# project-light.net
KiCad netlist of a schematic drawn in Altium Designer
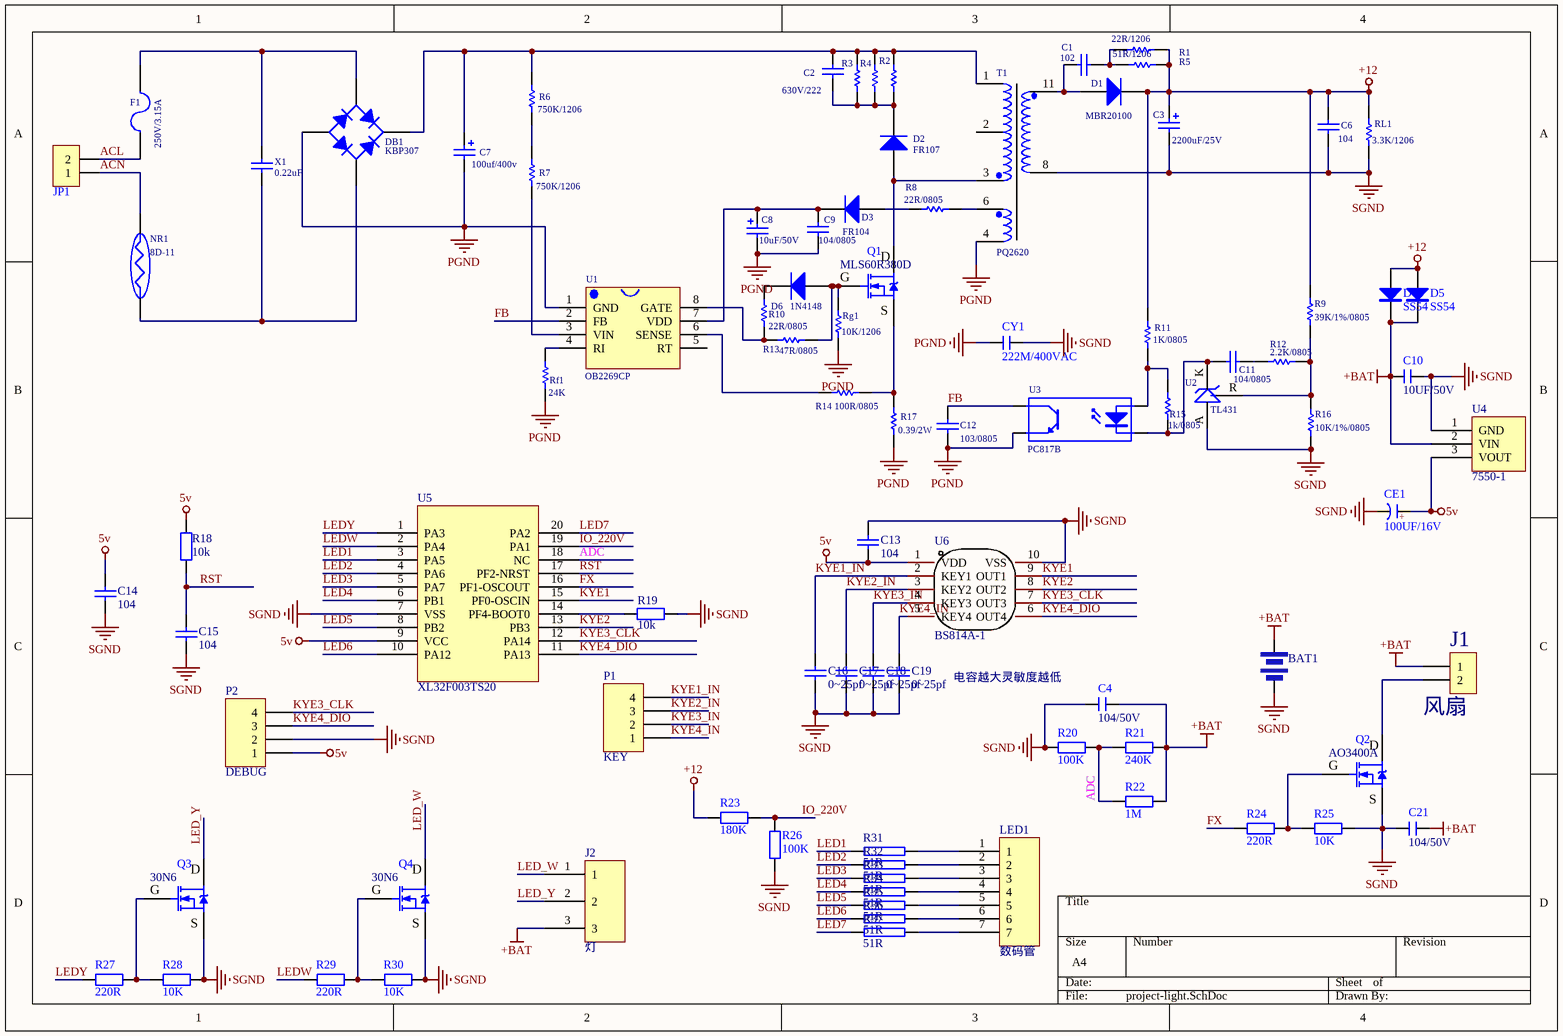
[diagram p0: project-light.SchDoc]

(export (version "E")
  (design (tool "Eeschema 10.0.6"))
  (components
    (comp (ref "BAT1") (value "~") (footprint "2pin") (libsource (lib "HOLIN") (part "BATTERY")))
    (comp (ref "C1")
      (value "102")
      (footprint "C 1206_l")
      (description "Capacitor")
      (fields (field (name "Comment") "472") (field (name "PUBLISHER") "Altium Limited"))
      (libsource (lib "Miscellaneous Devices") (part "Cap"))
    )
    (comp (ref "C2")
      (value "630V/222")
      (footprint "CBB=7.5MM")
      (description "Capacitor")
      (fields (field (name "PUBLISHER") "Altium Limited"))
      (libsource (lib "Miscellaneous Devices") (part "Cap"))
    )
    (comp (ref "C3")
      (value "2200uF/25V")
      (footprint "CAP 5.0*10*20-H - GD")
      (description "Polarized Capacitor (Axial)")
      (fields (field (name "PUBLISHER") "Altium Limited"))
      (libsource (lib "") (part "Cap Pol2_1"))
    )
    (comp (ref "C4")
      (value "104/50V")
      (footprint "C 0805_L")
      (description "瓷片电容")
      (libsource (lib "0.1 - 电阻-电容-电感") (part "CC"))
    )
    (comp (ref "C6")
      (value "104")
      (footprint "C 1206_l")
      (description "Capacitor")
      (fields (field (name "PUBLISHER") "Altium Limited"))
      (libsource (lib "Miscellaneous Devices") (part "Cap"))
    )
    (comp (ref "C7")
      (value "100uf/400v")
      (footprint "Cin /400V/56uF Wo")
      (description "Polarized Capacitor (Axial)")
      (fields (field (name "PUBLISHER") "Altium Limited"))
      (libsource (lib "Miscellaneous Devices") (part "Cap Pol2"))
    )
    (comp (ref "C8")
      (value "10uF/50V")
      (footprint "C Φ5*11 L=2.5")
      (description "Polarized Capacitor (Axial)")
      (fields (field (name "Comment") "47uF/50V") (field (name "PUBLISHER") "Altium Limited"))
      (libsource (lib "Miscellaneous Devices") (part "Cap Pol2"))
    )
    (comp (ref "C9")
      (value "104/0805")
      (footprint "C 0805_L")
      (description "Capacitor")
      (fields (field (name "PUBLISHER") "Altium Limited"))
      (libsource (lib "Miscellaneous Devices") (part "Cap"))
    )
    (comp (ref "C10")
      (value "10UF/50V")
      (footprint "C 0805_L")
      (description "瓷片电容")
      (libsource (lib "0.1 - 电阻-电容-电感") (part "CC"))
    )
    (comp (ref "C11")
      (value "104/0805")
      (footprint "C 0805_L")
      (description "Capacitor")
      (fields (field (name "PUBLISHER") "Altium Limited"))
      (libsource (lib "Miscellaneous Devices") (part "Cap"))
    )
    (comp (ref "C12")
      (value "103/0805")
      (footprint "C 0805_L")
      (description "Capacitor")
      (fields (field (name "PUBLISHER") "Altium Limited"))
      (libsource (lib "Miscellaneous Devices") (part "Cap"))
    )
    (comp (ref "C13")
      (value "104")
      (footprint "c 0805_l")
      (description "Capacitor")
      (fields (field (name "PUBLISHER") "Altium Limited"))
      (libsource (lib "Miscellaneous Devices") (part "Cap"))
    )
    (comp (ref "C14")
      (value "104")
      (footprint "C 0805_L")
      (description "Capacitor")
      (fields (field (name "PUBLISHER") "Altium Limited"))
      (libsource (lib "Miscellaneous Devices") (part "Cap"))
    )
    (comp (ref "C15")
      (value "104")
      (footprint "C 0805_L")
      (description "Capacitor")
      (fields (field (name "PUBLISHER") "Altium Limited"))
      (libsource (lib "Miscellaneous Devices") (part "Cap"))
    )
    (comp (ref "C16")
      (value "0~25pf")
      (footprint "C 0805_L")
      (description "Capacitor")
      (fields (field (name "PUBLISHER") "Altium Limited"))
      (libsource (lib "Miscellaneous Devices") (part "Cap"))
    )
    (comp (ref "C17")
      (value "0~25pf")
      (footprint "C 0805_L")
      (description "Capacitor")
      (fields (field (name "PUBLISHER") "Altium Limited"))
      (libsource (lib "Miscellaneous Devices") (part "Cap"))
    )
    (comp (ref "C18")
      (value "0~25pf")
      (footprint "C 0805_L")
      (description "Capacitor")
      (fields (field (name "PUBLISHER") "Altium Limited"))
      (libsource (lib "Miscellaneous Devices") (part "Cap"))
    )
    (comp (ref "C19")
      (value "0~25pf")
      (footprint "C 0805_L")
      (description "Capacitor")
      (fields (field (name "PUBLISHER") "Altium Limited"))
      (libsource (lib "Miscellaneous Devices") (part "Cap"))
    )
    (comp (ref "C21")
      (value "104/50V")
      (footprint "C 0805_L")
      (description "瓷片电容")
      (libsource (lib "0.1 - 电阻-电容-电感") (part "CC"))
    )
    (comp (ref "CE1")
      (value "100UF/16V")
      (footprint "CAP 2.5*6.3*11.2")
      (description "直插电解电容")
      (libsource (lib "0.1 - 电阻-电容-电感") (part "CE"))
    )
    (comp (ref "CY1")
      (value "222M/400VAC")
      (footprint "CY 7.5*8*4")
      (description "安规Y电容")
      (fields (field (name "版权归属") "封装库来自淘宝 ID：黄晶宝石"))
      (libsource (lib "0.1 - 电阻-电容-电感") (part "CY"))
    )
    (comp (ref "D1")
      (value "MBR20100")
      (footprint "TO252")
      (description "Silicon Low Leakage Diode")
      (fields (field (name "PUBLISHER") "Altium Limited"))
      (libsource (lib "Miscellaneous Devices") (part "Diode BAS116"))
    )
    (comp (ref "D2")
      (value "FR107")
      (footprint "D/SOD123")
      (description "Silicon Low Leakage Diode")
      (fields (field (name "PUBLISHER") "Altium Limited"))
      (libsource (lib "Miscellaneous Devices") (part "Diode BAS116"))
    )
    (comp (ref "D3")
      (value "FR104")
      (footprint "D/SOD123")
      (description "Silicon Low Leakage Diode")
      (fields (field (name "PUBLISHER") "Altium Limited"))
      (libsource (lib "Miscellaneous Devices") (part "Diode BAS116"))
    )
    (comp (ref "D4")
      (value "SS54")
      (footprint "SMA")
      (description "整流二极管")
      (libsource (lib "0.2 - 二极管-整流桥") (part "1N4007"))
    )
    (comp (ref "D5")
      (value "SS54")
      (footprint "SMA")
      (description "整流二极管")
      (libsource (lib "0.2 - 二极管-整流桥") (part "1N4007"))
    )
    (comp (ref "D6")
      (value "1N4148")
      (footprint "D 1N4148")
      (description "Silicon Low Leakage Diode")
      (fields (field (name "PUBLISHER") "Altium Limited"))
      (libsource (lib "") (part "Diode BAS116_1"))
    )
    (comp (ref "DB1")
      (value "KBP307")
      (footprint "DB D=1.1MM")
      (description "Full Wave Diode Bridge")
      (fields (field (name "PUBLISHER") "Altium Limited"))
      (libsource (lib "Miscellaneous Devices") (part "Bridge1"))
    )
    (comp (ref "F1")
      (value "250V/3.15A")
      (footprint "F 3.15A L=5MM")
      (description "Fuse")
      (fields (field (name "PUBLISHER") "Altium Limited"))
      (libsource (lib "Miscellaneous Devices") (part "Fuse 2"))
    )
    (comp (ref "J1")
      (value "风扇")
      (footprint "XH2.54-LI-2P")
      (description "Connector")
      (libsource (lib "*") (part "CON2"))
    )
    (comp (ref "J2") (value "灯") (footprint "HDR2.54-LI-3P") (libsource (lib "Schlib1") (part "Component_1")))
    (comp (ref "JP1")
      (value "HDR-1X2")
      (footprint "AC-027母座")
      (description "2P接插件")
      (fields (field (name "版权归属") "封装库来自淘宝 ID：黄晶宝石"))
      (libsource (lib "CFY01205") (part "Header 2"))
    )
    (comp (ref "LED1") (value "数码管") (footprint "1516数码管") (libsource (lib "CFY01205") (part "数码管")))
    (comp (ref "NR1") (value "8D-11") (footprint "NTC=7.5mm") (libsource (lib "12V5A") (part "NTC")))
    (comp (ref "P1")
      (value "KEY")
      (footprint "HDR1X4")
      (description "Header, 4-Pin")
      (fields (field (name "PUBLISHER") "Altium Limited"))
      (libsource (lib "Miscellaneous Connectors") (part "Header 4"))
    )
    (comp (ref "P2")
      (value "DEBUG")
      (footprint "HDR1X4")
      (description "Header, 4-Pin")
      (fields (field (name "PUBLISHER") "Altium Limited"))
      (libsource (lib "Miscellaneous Connectors") (part "Header 4"))
    )
    (comp (ref "Q1")
      (value "MLS60R380D")
      (footprint "TO252")
      (description "N沟场效应管")
      (libsource (lib "") (part "IRF840_1"))
    )
    (comp (ref "Q2")
      (value "AO3400A")
      (footprint "SOT-23")
      (description "N沟场效应管")
      (libsource (lib "0.5 - 场效应管-可控硅") (part "IRF840"))
    )
    (comp (ref "Q3")
      (value "30N6")
      (footprint "TO252")
      (description "N沟场效应管")
      (libsource (lib "") (part "IRF840_1"))
    )
    (comp (ref "Q4")
      (value "30N6")
      (footprint "TO252")
      (description "N沟场效应管")
      (libsource (lib "") (part "IRF840_1"))
    )
    (comp (ref "R1")
      (value "51R/1206")
      (footprint "r 1206_l")
      (description "Resistor")
      (fields (field (name "PUBLISHER") "Altium Limited"))
      (libsource (lib "Miscellaneous Devices") (part "Res1"))
    )
    (comp (ref "R2")
      (value "50K/2510/1W")
      (footprint "R 1206_L")
      (description "Resistor")
      (fields (field (name "PUBLISHER") "Altium Limited"))
      (libsource (lib "Miscellaneous Devices") (part "Res1"))
    )
    (comp (ref "R3")
      (value "50K/2510/1W")
      (footprint "R 1206_L")
      (description "Resistor")
      (fields (field (name "PUBLISHER") "Altium Limited"))
      (libsource (lib "Miscellaneous Devices") (part "Res1"))
    )
    (comp (ref "R4")
      (value "50K/2510/1W")
      (footprint "R 1206_L")
      (description "Resistor")
      (fields (field (name "PUBLISHER") "Altium Limited"))
      (libsource (lib "Miscellaneous Devices") (part "Res1"))
    )
    (comp (ref "R5")
      (value "22R/1206")
      (footprint "r 1206_l")
      (description "Resistor")
      (fields (field (name "PUBLISHER") "Altium Limited"))
      (libsource (lib "Miscellaneous Devices") (part "Res1"))
    )
    (comp (ref "R6")
      (value "750K/1206")
      (footprint "R 1206_L")
      (description "Resistor")
      (fields (field (name "PUBLISHER") "Altium Limited"))
      (libsource (lib "Miscellaneous Devices") (part "Res1"))
    )
    (comp (ref "R7")
      (value "750K/1206")
      (footprint "R 1206_L")
      (description "Resistor")
      (fields (field (name "PUBLISHER") "Altium Limited"))
      (libsource (lib "Miscellaneous Devices") (part "Res1"))
    )
    (comp (ref "R8")
      (value "22R/0805")
      (footprint "R 0805_L")
      (description "Resistor")
      (fields (field (name "PUBLISHER") "Altium Limited"))
      (libsource (lib "Miscellaneous Devices") (part "Res1"))
    )
    (comp (ref "R9")
      (value "39K/1%/0805")
      (footprint "R 0805_L")
      (description "Resistor")
      (fields (field (name "PUBLISHER") "Altium Limited"))
      (libsource (lib "Miscellaneous Devices") (part "Res1"))
    )
    (comp (ref "R10")
      (value "22R/0805")
      (footprint "R 0805_L")
      (description "Resistor")
      (fields (field (name "PUBLISHER") "Altium Limited"))
      (libsource (lib "Miscellaneous Devices") (part "Res1"))
    )
    (comp (ref "R11")
      (value "1K/0805")
      (footprint "R 0805_L")
      (description "Resistor")
      (fields (field (name "PUBLISHER") "Altium Limited"))
      (libsource (lib "Miscellaneous Devices") (part "Res1"))
    )
    (comp (ref "R12")
      (value "2.2K/0805")
      (footprint "R 0805_L")
      (description "Resistor")
      (fields (field (name "PUBLISHER") "Altium Limited"))
      (libsource (lib "Miscellaneous Devices") (part "Res1"))
    )
    (comp (ref "R13")
      (value "47R/0805")
      (footprint "R 0805_L")
      (description "Resistor")
      (fields (field (name "PUBLISHER") "Altium Limited"))
      (libsource (lib "Miscellaneous Devices") (part "Res1"))
    )
    (comp (ref "R14")
      (value "100R/0805")
      (footprint "R 0805_L")
      (description "Resistor")
      (fields (field (name "PUBLISHER") "Altium Limited"))
      (libsource (lib "Miscellaneous Devices") (part "Res1"))
    )
    (comp (ref "R15")
      (value "1k/0805")
      (footprint "R 0805_L")
      (description "Resistor")
      (fields (field (name "PUBLISHER") "Altium Limited"))
      (libsource (lib "Miscellaneous Devices") (part "Res1"))
    )
    (comp (ref "R16")
      (value "10K/1%/0805")
      (footprint "R 0805_L")
      (description "Resistor")
      (fields (field (name "Comment") "12.5K/1%/0805") (field (name "PUBLISHER") "Altium Limited"))
      (libsource (lib "Miscellaneous Devices") (part "Res1"))
    )
    (comp (ref "R17")
      (value "0.39/2W")
      (footprint "R 2512_L")
      (description "合金电阻")
      (fields (field (name "PUBLISHER") "Altium Limited"))
      (libsource (lib "Miscellaneous Devices") (part "Res1"))
    )
    (comp (ref "R18")
      (value "10k")
      (footprint "R 0805_L")
      (description "Resistor")
      (fields (field (name "PUBLISHER") "Altium Limited"))
      (libsource (lib "Miscellaneous Devices") (part "Res2"))
    )
    (comp (ref "R19")
      (value "10k")
      (footprint "R 0805_L")
      (description "Resistor")
      (fields (field (name "PUBLISHER") "Altium Limited"))
      (libsource (lib "") (part "Res2_1"))
    )
    (comp (ref "R20")
      (value "100K")
      (footprint "R 0805_L")
      (description "色环电阻")
      (fields (field (name "版权归属") "封装库来自淘宝 ID：黄晶宝石"))
      (libsource (lib "0.1 - 电阻-电容-电感") (part "R-S"))
    )
    (comp (ref "R21")
      (value "240K")
      (footprint "R 0805_L")
      (description "色环电阻")
      (fields (field (name "版权归属") "封装库来自淘宝 ID：黄晶宝石"))
      (libsource (lib "0.1 - 电阻-电容-电感") (part "R-S"))
    )
    (comp (ref "R22")
      (value "1M")
      (footprint "R 0805_L")
      (description "色环电阻")
      (fields (field (name "版权归属") "封装库来自淘宝 ID：黄晶宝石"))
      (libsource (lib "0.1 - 电阻-电容-电感") (part "R-S"))
    )
    (comp (ref "R23")
      (value "180K")
      (footprint "R 0805_L")
      (description "色环电阻")
      (fields (field (name "版权归属") "封装库来自淘宝 ID：黄晶宝石"))
      (libsource (lib "0.1 - 电阻-电容-电感") (part "R-S"))
    )
    (comp (ref "R24")
      (value "220R")
      (footprint "R 0805_L")
      (description "色环电阻")
      (fields (field (name "版权归属") "封装库来自淘宝 ID：黄晶宝石"))
      (libsource (lib "0.1 - 电阻-电容-电感") (part "R-S"))
    )
    (comp (ref "R25")
      (value "10K")
      (footprint "R 0805_L")
      (description "色环电阻")
      (fields (field (name "版权归属") "封装库来自淘宝 ID：黄晶宝石"))
      (libsource (lib "0.1 - 电阻-电容-电感") (part "R-S"))
    )
    (comp (ref "R26")
      (value "100K")
      (footprint "R 0805_L")
      (description "色环电阻")
      (fields (field (name "版权归属") "封装库来自淘宝 ID：黄晶宝石"))
      (libsource (lib "0.1 - 电阻-电容-电感") (part "R-S"))
    )
    (comp (ref "R27")
      (value "220R")
      (footprint "R 0805_L")
      (description "色环电阻")
      (fields (field (name "版权归属") "封装库来自淘宝 ID：黄晶宝石"))
      (libsource (lib "0.1 - 电阻-电容-电感") (part "R-S"))
    )
    (comp (ref "R28")
      (value "10K")
      (footprint "R 0805_L")
      (description "色环电阻")
      (fields (field (name "版权归属") "封装库来自淘宝 ID：黄晶宝石"))
      (libsource (lib "0.1 - 电阻-电容-电感") (part "R-S"))
    )
    (comp (ref "R29")
      (value "220R")
      (footprint "R 0805_L")
      (description "色环电阻")
      (fields (field (name "版权归属") "封装库来自淘宝 ID：黄晶宝石"))
      (libsource (lib "0.1 - 电阻-电容-电感") (part "R-S"))
    )
    (comp (ref "R30")
      (value "10K")
      (footprint "R 0805_L")
      (description "色环电阻")
      (fields (field (name "版权归属") "封装库来自淘宝 ID：黄晶宝石"))
      (libsource (lib "0.1 - 电阻-电容-电感") (part "R-S"))
    )
    (comp (ref "R31") (value "51R") (footprint "R 0805_L") (libsource (lib "HOLIN") (part "RES2")))
    (comp (ref "R32") (value "51R") (footprint "R 0805_L") (libsource (lib "HOLIN") (part "RES2")))
    (comp (ref "R33") (value "51R") (footprint "R 0805_L") (libsource (lib "HOLIN") (part "RES2")))
    (comp (ref "R34") (value "51R") (footprint "R 0805_L") (libsource (lib "HOLIN") (part "RES2")))
    (comp (ref "R35") (value "51R") (footprint "R 0805_L") (libsource (lib "HOLIN") (part "RES2")))
    (comp (ref "R36") (value "51R") (footprint "R 0805_L") (libsource (lib "HOLIN") (part "RES2")))
    (comp (ref "R37") (value "51R") (footprint "R 0805_L") (libsource (lib "HOLIN") (part "RES2")))
    (comp (ref "Rf1")
      (value "24K")
      (footprint "R 0805_L")
      (description "Resistor")
      (fields (field (name "Comment") "Res1") (field (name "PUBLISHER") "Altium Limited"))
      (libsource (lib "Miscellaneous Devices") (part "Res1"))
    )
    (comp (ref "Rg1")
      (value "10K/1206")
      (footprint "R 1206_L")
      (description "Resistor")
      (fields (field (name "Comment") "10K/0805") (field (name "PUBLISHER") "Altium Limited"))
      (libsource (lib "Miscellaneous Devices") (part "Res1"))
    )
    (comp (ref "RL1")
      (value "3.3K/1206")
      (footprint "r 1206_l")
      (description "Resistor")
      (fields (field (name "PUBLISHER") "Altium Limited"))
      (libsource (lib "Miscellaneous Devices") (part "Res1"))
    )
    (comp (ref "T1") (value "PQ2620") (footprint "T PQ2620") (libsource (lib "12V5A") (part "T")))
    (comp (ref "U1") (value "OB2269CP") (footprint "OB2269") (libsource (lib "12V5A") (part "OB2269CP")))
    (comp (ref "U2")
      (value "TL431")
      (footprint "LC-SOT-23(SOT-23-3)")
      (libsource (lib "12V5A") (part "TL431"))
    )
    (comp (ref "U3")
      (value "PC817B")
      (footprint "LC-SMD-4")
      (description "4-Pin Phototransistor Optocoupler")
      (fields (field (name "PUBLISHER") "Altium Limited"))
      (libsource (lib "Miscellaneous Devices") (part "Optoisolator1"))
    )
    (comp (ref "U4") (value "7550-1") (footprint "SOT-89") (libsource (lib "CFY01205") (part "7550-1")))
    (comp (ref "U5")
      (value "XL32F003TS20")
      (footprint "TSSOP20")
      (libsource (lib "X30BV2_Library") (part "XL32F003"))
    )
    (comp (ref "U6")
      (value "BS814A-1")
      (footprint "MSOP-10")
      (fields (field (name "NAME") "BS814A-1") (field (name "MANUFACTURER") "HOLTEK(合泰/盛群)"))
      (libsource (lib "altium-import") (part "root_0_BS814A-1_"))
    )
    (comp (ref "X1")
      (value "0.22uF")
      (footprint "CX=10mm")
      (description "Capacitor")
      (fields (field (name "Comment") "224") (field (name "PUBLISHER") "Altium Limited"))
      (libsource (lib "Miscellaneous Devices") (part "Cap"))
    )
  )
  (nets
    (net (code "1") (name "+12") (class "Default")
      (node (ref "C3") (pin "1") (pinfunction "2_1") (pintype "passive"))
      (node (ref "C6") (pin "1") (pinfunction "1_1") (pintype "passive"))
      (node (ref "D1") (pin "2") (pinfunction "K_2") (pintype "passive"))
      (node (ref "D4") (pin "1") (pinfunction "A_1") (pintype "passive"))
      (node (ref "D5") (pin "1") (pinfunction "A_1") (pintype "passive"))
      (node (ref "R1") (pin "1") (pinfunction "1_1") (pintype "passive"))
      (node (ref "R11") (pin "2") (pinfunction "2_2") (pintype "passive"))
      (node (ref "R23") (pin "2") (pinfunction "2_2") (pintype "passive"))
      (node (ref "R5") (pin "1") (pinfunction "1_1") (pintype "passive"))
      (node (ref "R9") (pin "2") (pinfunction "2_2") (pintype "passive"))
      (node (ref "RL1") (pin "2") (pinfunction "2_2") (pintype "passive"))
    )
    (net (code "2") (name "+BAT") (class "Default")
      (node (ref "BAT1") (pin "1") (pinfunction "1_1") (pintype "passive"))
      (node (ref "C10") (pin "2") (pinfunction "2_2") (pintype "passive"))
      (node (ref "C21") (pin "2") (pinfunction "2_2") (pintype "passive"))
      (node (ref "C4") (pin "1") (pinfunction "1_1") (pintype "passive"))
      (node (ref "D4") (pin "2") (pinfunction "K_2") (pintype "passive"))
      (node (ref "D5") (pin "2") (pinfunction "K_2") (pintype "passive"))
      (node (ref "J1") (pin "1") (pinfunction "1_1") (pintype "passive"))
      (node (ref "J2") (pin "3") (pinfunction "3_3") (pintype "passive"))
      (node (ref "R21") (pin "1") (pinfunction "1_1") (pintype "passive"))
      (node (ref "R22") (pin "2") (pinfunction "2_2") (pintype "passive"))
      (node (ref "U4") (pin "2") (pinfunction "VIN_2") (pintype "passive"))
    )
    (net (code "3") (name "/ACL") (class "Default")
      (node (ref "F1") (pin "1") (pinfunction "1_1") (pintype "passive"))
      (node (ref "JP1") (pin "2") (pinfunction "2_2") (pintype "passive"))
    )
    (net (code "4") (name "/ACN") (class "Default")
      (node (ref "JP1") (pin "1") (pinfunction "1_1") (pintype "passive"))
      (node (ref "NR1") (pin "1") (pinfunction "1_1") (pintype "passive"))
    )
    (net (code "5") (name "/ADC") (class "Default")
      (node (ref "R20") (pin "1") (pinfunction "1_1") (pintype "passive"))
      (node (ref "R21") (pin "2") (pinfunction "2_2") (pintype "passive"))
      (node (ref "R22") (pin "1") (pinfunction "1_1") (pintype "passive"))
      (node (ref "U5") (pin "18") (pinfunction "NC_18") (pintype "passive"))
    )
    (net (code "6") (name "/FB") (class "Default")
      (node (ref "C12") (pin "2") (pinfunction "2_2") (pintype "passive"))
      (node (ref "U1") (pin "2") (pinfunction "FB_2") (pintype "passive"))
      (node (ref "U3") (pin "C") (pinfunction "C_C") (pintype "passive"))
    )
    (net (code "7") (name "/FX") (class "Default")
      (node (ref "R24") (pin "2") (pinfunction "2_2") (pintype "passive"))
      (node (ref "U5") (pin "16") (pinfunction "PF1-OSCOUT_16") (pintype "passive"))
    )
    (net (code "8") (name "/IO_220V") (class "Default")
      (node (ref "R23") (pin "1") (pinfunction "1_1") (pintype "passive"))
      (node (ref "R26") (pin "2") (pinfunction "2_2") (pintype "passive"))
      (node (ref "U5") (pin "19") (pinfunction "PA1_19") (pintype "passive"))
    )
    (net (code "9") (name "/KYE1") (class "Default")
      (node (ref "U5") (pin "15") (pinfunction "PF0-OSCIN_15") (pintype "passive"))
      (node (ref "U6") (pin "9") (pinfunction "OUT1_9") (pintype "passive"))
    )
    (net (code "10") (name "/KYE1_IN") (class "Default")
      (node (ref "C16") (pin "2") (pinfunction "2_2") (pintype "passive"))
      (node (ref "P1") (pin "4") (pinfunction "4_4") (pintype "passive"))
      (node (ref "U6") (pin "2") (pinfunction "KEY1_2") (pintype "passive"))
    )
    (net (code "11") (name "/KYE2") (class "Default")
      (node (ref "U5") (pin "13") (pinfunction "PB3_13") (pintype "passive"))
      (node (ref "U6") (pin "8") (pinfunction "OUT2_8") (pintype "passive"))
    )
    (net (code "12") (name "/KYE2_IN") (class "Default")
      (node (ref "C17") (pin "2") (pinfunction "2_2") (pintype "passive"))
      (node (ref "P1") (pin "3") (pinfunction "3_3") (pintype "passive"))
      (node (ref "U6") (pin "3") (pinfunction "KEY2_3") (pintype "passive"))
    )
    (net (code "13") (name "/KYE3_CLK") (class "Default")
      (node (ref "P2") (pin "4") (pinfunction "4_4") (pintype "passive"))
      (node (ref "U5") (pin "12") (pinfunction "PA14_12") (pintype "passive"))
      (node (ref "U6") (pin "7") (pinfunction "OUT3_7") (pintype "passive"))
    )
    (net (code "14") (name "/KYE3_IN") (class "Default")
      (node (ref "C18") (pin "2") (pinfunction "2_2") (pintype "passive"))
      (node (ref "P1") (pin "2") (pinfunction "2_2") (pintype "passive"))
      (node (ref "U6") (pin "4") (pinfunction "KEY3_4") (pintype "passive"))
    )
    (net (code "15") (name "/KYE4_DIO") (class "Default")
      (node (ref "P2") (pin "3") (pinfunction "3_3") (pintype "passive"))
      (node (ref "U5") (pin "11") (pinfunction "PA13_11") (pintype "passive"))
      (node (ref "U6") (pin "6") (pinfunction "OUT4_6") (pintype "passive"))
    )
    (net (code "16") (name "/KYE4_IN") (class "Default")
      (node (ref "C19") (pin "2") (pinfunction "2_2") (pintype "passive"))
      (node (ref "P1") (pin "1") (pinfunction "1_1") (pintype "passive"))
      (node (ref "U6") (pin "5") (pinfunction "KEY4_5") (pintype "passive"))
    )
    (net (code "17") (name "/LED1") (class "Default")
      (node (ref "R31") (pin "2") (pintype "passive"))
      (node (ref "U5") (pin "3") (pinfunction "PA5_3") (pintype "passive"))
    )
    (net (code "18") (name "/LED2") (class "Default")
      (node (ref "R32") (pin "2") (pintype "passive"))
      (node (ref "U5") (pin "4") (pinfunction "PA6_4") (pintype "passive"))
    )
    (net (code "19") (name "/LED3") (class "Default")
      (node (ref "R33") (pin "2") (pintype "passive"))
      (node (ref "U5") (pin "5") (pinfunction "PA7_5") (pintype "passive"))
    )
    (net (code "20") (name "/LED4") (class "Default")
      (node (ref "R34") (pin "2") (pintype "passive"))
      (node (ref "U5") (pin "6") (pinfunction "PB1_6") (pintype "passive"))
    )
    (net (code "21") (name "/LED5") (class "Default")
      (node (ref "R35") (pin "2") (pintype "passive"))
      (node (ref "U5") (pin "8") (pinfunction "PB2_8") (pintype "passive"))
    )
    (net (code "22") (name "/LED6") (class "Default")
      (node (ref "R36") (pin "2") (pintype "passive"))
      (node (ref "U5") (pin "10") (pinfunction "PA12_10") (pintype "passive"))
    )
    (net (code "23") (name "/LED7") (class "Default")
      (node (ref "R37") (pin "2") (pintype "passive"))
      (node (ref "U5") (pin "20") (pinfunction "PA2_20") (pintype "passive"))
    )
    (net (code "24") (name "/LEDW") (class "Default")
      (node (ref "R29") (pin "2") (pinfunction "2_2") (pintype "passive"))
      (node (ref "U5") (pin "2") (pinfunction "PA4_2") (pintype "passive"))
    )
    (net (code "25") (name "/LEDY") (class "Default")
      (node (ref "R27") (pin "2") (pinfunction "2_2") (pintype "passive"))
      (node (ref "U5") (pin "1") (pinfunction "PA3_1") (pintype "passive"))
    )
    (net (code "26") (name "/LED_W") (class "Default")
      (node (ref "J2") (pin "1") (pinfunction "1_1") (pintype "passive"))
      (node (ref "Q4") (pin "2") (pinfunction "D_2") (pintype "passive"))
    )
    (net (code "27") (name "/LED_Y") (class "Default")
      (node (ref "J2") (pin "2") (pinfunction "2_2") (pintype "passive"))
      (node (ref "Q3") (pin "2") (pinfunction "D_2") (pintype "passive"))
    )
    (net (code "28") (name "/RST") (class "Default")
      (node (ref "C15") (pin "1") (pinfunction "1_1") (pintype "passive"))
      (node (ref "R18") (pin "1") (pinfunction "1_1") (pintype "passive"))
      (node (ref "U5") (pin "17") (pinfunction "PF2-NRST_17") (pintype "passive"))
    )
    (net (code "29") (name "5v") (class "Default")
      (node (ref "C13") (pin "2") (pinfunction "2_2") (pintype "passive"))
      (node (ref "C14") (pin "1") (pinfunction "1_1") (pintype "passive"))
      (node (ref "CE1") (pin "1") (pinfunction "A_1") (pintype "passive"))
      (node (ref "P2") (pin "1") (pinfunction "1_1") (pintype "passive"))
      (node (ref "R18") (pin "2") (pinfunction "2_2") (pintype "passive"))
      (node (ref "U4") (pin "3") (pinfunction "VOUT_3") (pintype "passive"))
      (node (ref "U5") (pin "9") (pinfunction "VCC_9") (pintype "passive"))
      (node (ref "U6") (pin "1") (pinfunction "VDD_1") (pintype "passive"))
    )
    (net (code "30") (name "Net-(C1-Pad2)") (class "Default")
      (node (ref "C1") (pin "2") (pinfunction "2_2") (pintype "passive"))
      (node (ref "R1") (pin "2") (pinfunction "2_2") (pintype "passive"))
      (node (ref "R5") (pin "2") (pinfunction "2_2") (pintype "passive"))
    )
    (net (code "31") (name "Net-(C11-Pad1)") (class "Default")
      (node (ref "C11") (pin "1") (pinfunction "1_1") (pintype "passive"))
      (node (ref "R15") (pin "1") (pinfunction "1_1") (pintype "passive"))
      (node (ref "U2") (pin "K") (pinfunction "K_K") (pintype "passive"))
      (node (ref "U3") (pin "K") (pinfunction "K_K") (pintype "passive"))
    )
    (net (code "32") (name "Net-(C11-Pad2)") (class "Default")
      (node (ref "C11") (pin "2") (pinfunction "2_2") (pintype "passive"))
      (node (ref "R12") (pin "2") (pinfunction "2_2") (pintype "passive"))
    )
    (net (code "33") (name "Net-(D1-A)") (class "Default")
      (node (ref "C1") (pin "1") (pinfunction "1_1") (pintype "passive"))
      (node (ref "D1") (pin "1") (pinfunction "A_1") (pintype "passive"))
      (node (ref "T1") (pin "11") (pinfunction "6_11") (pintype "passive"))
    )
    (net (code "34") (name "Net-(D2-A)") (class "Default")
      (node (ref "D2") (pin "1") (pinfunction "A_1") (pintype "passive"))
      (node (ref "Q1") (pin "2") (pinfunction "D_2") (pintype "passive"))
      (node (ref "T1") (pin "3") (pintype "passive"))
    )
    (net (code "35") (name "Net-(D2-K)") (class "Default")
      (node (ref "C2") (pin "2") (pinfunction "2_2") (pintype "passive"))
      (node (ref "D2") (pin "2") (pinfunction "K_2") (pintype "passive"))
      (node (ref "R2") (pin "2") (pinfunction "2_2") (pintype "passive"))
      (node (ref "R3") (pin "2") (pinfunction "2_2") (pintype "passive"))
      (node (ref "R4") (pin "2") (pinfunction "2_2") (pintype "passive"))
    )
    (net (code "36") (name "Net-(D3-A)") (class "Default")
      (node (ref "D3") (pin "1") (pinfunction "A_1") (pintype "passive"))
      (node (ref "R8") (pin "2") (pinfunction "2_2") (pintype "passive"))
    )
    (net (code "37") (name "Net-(D3-K)") (class "Default")
      (node (ref "C8") (pin "1") (pinfunction "1_1") (pintype "passive"))
      (node (ref "C9") (pin "1") (pinfunction "1_1") (pintype "passive"))
      (node (ref "D3") (pin "2") (pinfunction "K_2") (pintype "passive"))
      (node (ref "U1") (pin "7") (pinfunction "VDD_7") (pintype "passive"))
    )
    (net (code "38") (name "Net-(D6-A)") (class "Default")
      (node (ref "D6") (pin "+") (pinfunction "A_+") (pintype "passive"))
      (node (ref "Q1") (pin "1") (pinfunction "G_1") (pintype "passive"))
      (node (ref "R13") (pin "1") (pinfunction "1_1") (pintype "passive"))
      (node (ref "Rg1") (pin "1") (pinfunction "1_1") (pintype "passive"))
    )
    (net (code "39") (name "Net-(D6-K)") (class "Default")
      (node (ref "D6") (pin "-") (pinfunction "K_-") (pintype "passive"))
      (node (ref "R10") (pin "1") (pinfunction "1_1") (pintype "passive"))
    )
    (net (code "40") (name "Net-(DB1-1)") (class "Default")
      (node (ref "C2") (pin "1") (pinfunction "1_1") (pintype "passive"))
      (node (ref "C7") (pin "1") (pinfunction "1_1") (pintype "passive"))
      (node (ref "DB1") (pin "+") (pinfunction "1_+") (pintype "passive"))
      (node (ref "R2") (pin "1") (pinfunction "1_1") (pintype "passive"))
      (node (ref "R3") (pin "1") (pinfunction "1_1") (pintype "passive"))
      (node (ref "R4") (pin "1") (pinfunction "1_1") (pintype "passive"))
      (node (ref "R6") (pin "2") (pinfunction "2_2") (pintype "passive"))
      (node (ref "T1") (pin "1") (pintype "passive"))
    )
    (net (code "41") (name "Net-(DB1-3)") (class "Default")
      (node (ref "DB1") (pin "N") (pinfunction "3_N") (pintype "passive"))
      (node (ref "NR1") (pin "2") (pinfunction "2_2") (pintype "passive"))
      (node (ref "X1") (pin "1") (pinfunction "1_1") (pintype "passive"))
    )
    (net (code "42") (name "Net-(DB1-4)") (class "Default")
      (node (ref "DB1") (pin "L") (pinfunction "4_L") (pintype "passive"))
      (node (ref "F1") (pin "2") (pinfunction "2_2") (pintype "passive"))
      (node (ref "X1") (pin "2") (pinfunction "2_2") (pintype "passive"))
    )
    (net (code "43") (name "Net-(LED1-Pad1)") (class "Default")
      (node (ref "LED1") (pin "1") (pinfunction "1_1") (pintype "passive"))
      (node (ref "R31") (pin "1") (pintype "passive"))
    )
    (net (code "44") (name "Net-(LED1-Pad2)") (class "Default")
      (node (ref "LED1") (pin "2") (pinfunction "2_2") (pintype "passive"))
      (node (ref "R32") (pin "1") (pintype "passive"))
    )
    (net (code "45") (name "Net-(LED1-Pad3)") (class "Default")
      (node (ref "LED1") (pin "3") (pinfunction "3_3") (pintype "passive"))
      (node (ref "R33") (pin "1") (pintype "passive"))
    )
    (net (code "46") (name "Net-(LED1-Pad4)") (class "Default")
      (node (ref "LED1") (pin "4") (pinfunction "4_4") (pintype "passive"))
      (node (ref "R34") (pin "1") (pintype "passive"))
    )
    (net (code "47") (name "Net-(LED1-Pad5)") (class "Default")
      (node (ref "LED1") (pin "5") (pinfunction "5_5") (pintype "passive"))
      (node (ref "R35") (pin "1") (pintype "passive"))
    )
    (net (code "48") (name "Net-(LED1-Pad6)") (class "Default")
      (node (ref "LED1") (pin "6") (pinfunction "6_6") (pintype "passive"))
      (node (ref "R36") (pin "1") (pintype "passive"))
    )
    (net (code "49") (name "Net-(LED1-Pad7)") (class "Default")
      (node (ref "LED1") (pin "7") (pinfunction "7_7") (pintype "passive"))
      (node (ref "R37") (pin "1") (pintype "passive"))
    )
    (net (code "50") (name "Net-(Q1-S)") (class "Default")
      (node (ref "Q1") (pin "3") (pinfunction "S_3") (pintype "passive"))
      (node (ref "R14") (pin "1") (pinfunction "1_1") (pintype "passive"))
      (node (ref "R17") (pin "2") (pinfunction "2_2") (pintype "passive"))
    )
    (net (code "51") (name "Net-(Q2-D)") (class "Default")
      (node (ref "J1") (pin "2") (pinfunction "2_2") (pintype "passive"))
      (node (ref "Q2") (pin "3") (pinfunction "D_3") (pintype "passive"))
    )
    (net (code "52") (name "Net-(Q2-G)") (class "Default")
      (node (ref "Q2") (pin "1") (pinfunction "G_1") (pintype "passive"))
      (node (ref "R24") (pin "1") (pinfunction "1_1") (pintype "passive"))
      (node (ref "R25") (pin "2") (pinfunction "2_2") (pintype "passive"))
    )
    (net (code "53") (name "Net-(Q3-G)") (class "Default")
      (node (ref "Q3") (pin "1") (pinfunction "G_1") (pintype "passive"))
      (node (ref "R27") (pin "1") (pinfunction "1_1") (pintype "passive"))
      (node (ref "R28") (pin "2") (pinfunction "2_2") (pintype "passive"))
    )
    (net (code "54") (name "Net-(Q4-G)") (class "Default")
      (node (ref "Q4") (pin "1") (pinfunction "G_1") (pintype "passive"))
      (node (ref "R29") (pin "1") (pinfunction "1_1") (pintype "passive"))
      (node (ref "R30") (pin "2") (pinfunction "2_2") (pintype "passive"))
    )
    (net (code "55") (name "Net-(R6-Pad1)") (class "Default")
      (node (ref "R6") (pin "1") (pinfunction "1_1") (pintype "passive"))
      (node (ref "R7") (pin "2") (pinfunction "2_2") (pintype "passive"))
    )
    (net (code "56") (name "Net-(R8-Pad1)") (class "Default")
      (node (ref "R8") (pin "1") (pinfunction "1_1") (pintype "passive"))
      (node (ref "T1") (pin "6") (pintype "passive"))
    )
    (net (code "57") (name "Net-(R11-Pad1)") (class "Default")
      (node (ref "R11") (pin "1") (pinfunction "1_1") (pintype "passive"))
      (node (ref "R15") (pin "2") (pinfunction "2_2") (pintype "passive"))
      (node (ref "U3") (pin "A") (pinfunction "A_A") (pintype "passive"))
    )
    (net (code "58") (name "Net-(R12-Pad1)") (class "Default")
      (node (ref "R12") (pin "1") (pinfunction "1_1") (pintype "passive"))
      (node (ref "R16") (pin "2") (pinfunction "2_2") (pintype "passive"))
      (node (ref "R9") (pin "1") (pinfunction "1_1") (pintype "passive"))
      (node (ref "U2") (pin "R") (pinfunction "R_R") (pintype "passive"))
    )
    (net (code "59") (name "Net-(U1-GATE)") (class "Default")
      (node (ref "R10") (pin "2") (pinfunction "2_2") (pintype "passive"))
      (node (ref "R13") (pin "2") (pinfunction "2_2") (pintype "passive"))
      (node (ref "U1") (pin "8") (pinfunction "GATE_8") (pintype "passive"))
    )
    (net (code "60") (name "Net-(U1-RI)") (class "Default")
      (node (ref "Rf1") (pin "1") (pinfunction "1_1") (pintype "passive"))
      (node (ref "U1") (pin "4") (pinfunction "RI_4") (pintype "passive"))
    )
    (net (code "61") (name "Net-(U1-SENSE)") (class "Default")
      (node (ref "R14") (pin "2") (pinfunction "2_2") (pintype "passive"))
      (node (ref "U1") (pin "6") (pinfunction "SENSE_6") (pintype "passive"))
    )
    (net (code "62") (name "Net-(U1-VIN)") (class "Default")
      (node (ref "R7") (pin "1") (pinfunction "1_1") (pintype "passive"))
      (node (ref "U1") (pin "3") (pinfunction "VIN_3") (pintype "passive"))
    )
    (net (code "63") (name "Net-(U5-PF4-BOOT0)") (class "Default")
      (node (ref "R19") (pin "2") (pinfunction "2_2") (pintype "passive"))
      (node (ref "U5") (pin "14") (pinfunction "PF4-BOOT0_14") (pintype "passive"))
    )
    (net (code "64") (name "PGND") (class "Default")
      (node (ref "C12") (pin "1") (pinfunction "1_1") (pintype "passive"))
      (node (ref "C7") (pin "2") (pinfunction "2_2") (pintype "passive"))
      (node (ref "C8") (pin "2") (pinfunction "2_2") (pintype "passive"))
      (node (ref "C9") (pin "2") (pinfunction "2_2") (pintype "passive"))
      (node (ref "CY1") (pin "2") (pinfunction "2_2") (pintype "passive"))
      (node (ref "DB1") (pin "-") (pinfunction "2_-") (pintype "passive"))
      (node (ref "R17") (pin "1") (pinfunction "1_1") (pintype "passive"))
      (node (ref "Rf1") (pin "2") (pinfunction "2_2") (pintype "passive"))
      (node (ref "Rg1") (pin "2") (pinfunction "2_2") (pintype "passive"))
      (node (ref "T1") (pin "4") (pinfunction "4_4") (pintype "passive"))
      (node (ref "U1") (pin "1") (pinfunction "GND_1") (pintype "passive"))
      (node (ref "U3") (pin "E") (pinfunction "E_E") (pintype "passive"))
    )
    (net (code "65") (name "SGND") (class "Default")
      (node (ref "BAT1") (pin "2") (pinfunction "2_2") (pintype "passive"))
      (node (ref "C10") (pin "1") (pinfunction "1_1") (pintype "passive"))
      (node (ref "C13") (pin "1") (pinfunction "1_1") (pintype "passive"))
      (node (ref "C14") (pin "2") (pinfunction "2_2") (pintype "passive"))
      (node (ref "C15") (pin "2") (pinfunction "2_2") (pintype "passive"))
      (node (ref "C16") (pin "1") (pinfunction "1_1") (pintype "passive"))
      (node (ref "C17") (pin "1") (pinfunction "1_1") (pintype "passive"))
      (node (ref "C18") (pin "1") (pinfunction "1_1") (pintype "passive"))
      (node (ref "C19") (pin "1") (pinfunction "1_1") (pintype "passive"))
      (node (ref "C21") (pin "1") (pinfunction "1_1") (pintype "passive"))
      (node (ref "C3") (pin "2") (pinfunction "1_2") (pintype "passive"))
      (node (ref "C4") (pin "2") (pinfunction "2_2") (pintype "passive"))
      (node (ref "C6") (pin "2") (pinfunction "2_2") (pintype "passive"))
      (node (ref "CE1") (pin "2") (pinfunction "K_2") (pintype "passive"))
      (node (ref "CY1") (pin "1") (pinfunction "1_1") (pintype "passive"))
      (node (ref "P2") (pin "2") (pinfunction "2_2") (pintype "passive"))
      (node (ref "Q2") (pin "2") (pinfunction "S_2") (pintype "passive"))
      (node (ref "Q3") (pin "3") (pinfunction "S_3") (pintype "passive"))
      (node (ref "Q4") (pin "3") (pinfunction "S_3") (pintype "passive"))
      (node (ref "R16") (pin "1") (pinfunction "1_1") (pintype "passive"))
      (node (ref "R19") (pin "1") (pinfunction "1_1") (pintype "passive"))
      (node (ref "R20") (pin "2") (pinfunction "2_2") (pintype "passive"))
      (node (ref "R25") (pin "1") (pinfunction "1_1") (pintype "passive"))
      (node (ref "R26") (pin "1") (pinfunction "1_1") (pintype "passive"))
      (node (ref "R28") (pin "1") (pinfunction "1_1") (pintype "passive"))
      (node (ref "R30") (pin "1") (pinfunction "1_1") (pintype "passive"))
      (node (ref "RL1") (pin "1") (pinfunction "1_1") (pintype "passive"))
      (node (ref "T1") (pin "8") (pintype "passive"))
      (node (ref "U2") (pin "A") (pinfunction "A_A") (pintype "passive"))
      (node (ref "U4") (pin "1") (pinfunction "GND_1") (pintype "passive"))
      (node (ref "U5") (pin "7") (pinfunction "VSS_7") (pintype "passive"))
      (node (ref "U6") (pin "10") (pinfunction "VSS_10") (pintype "passive"))
    )
    (net (code "66") (name "unconnected-(T1-Pad2)") (class "Default")
      (node (ref "T1") (pin "2") (pintype "passive"))
    )
    (net (code "67") (name "unconnected-(U1-RT-Pad5)") (class "Default")
      (node (ref "U1") (pin "5") (pinfunction "RT_5") (pintype "passive"))
    )
  )
)
